# Galaxydrive.net
KiCad netlist of a schematic drawn in EAGLE
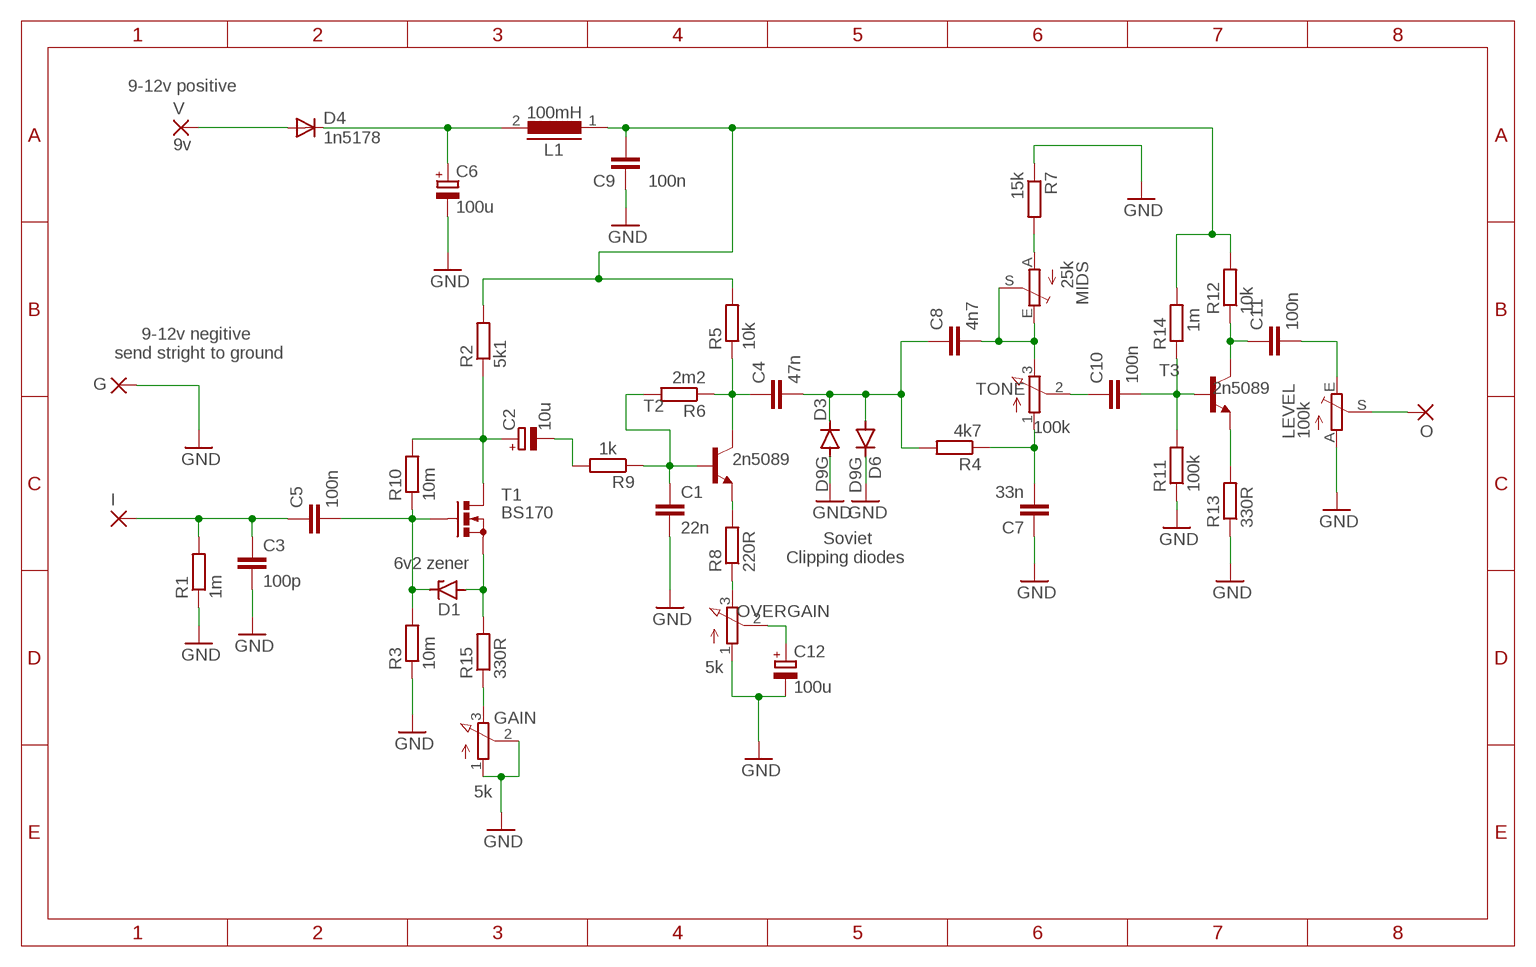
[diagram p0: schematic, sheet 1]

(export (version "E")
  (design (tool "Eeschema 10.0.6"))
  (components
    (comp (ref "C1")
      (value "22n")
      (footprint "eagle-import:C5B2.5")
      (libsource (lib "eagle-import") (part "C5/2.5"))
    )
    (comp (ref "C2")
      (value "10u")
      (footprint "eagle-import:E1,8-4")
      (libsource (lib "eagle-import") (part "CPOL-EUE1.8-4"))
    )
    (comp (ref "C3")
      (value "100p")
      (footprint "eagle-import:C5B2.5")
      (libsource (lib "eagle-import") (part "C5/2.5"))
    )
    (comp (ref "C4")
      (value "47n")
      (footprint "eagle-import:C5B2.5")
      (libsource (lib "eagle-import") (part "C5/2.5"))
    )
    (comp (ref "C5")
      (value "100n")
      (footprint "eagle-import:C5B2.5")
      (libsource (lib "eagle-import") (part "C5/2.5"))
    )
    (comp (ref "C6")
      (value "100u")
      (footprint "eagle-import:E2-4")
      (libsource (lib "eagle-import") (part "CPOL-EUE2-4"))
    )
    (comp (ref "C7")
      (value "33n")
      (footprint "eagle-import:C5B2.5")
      (libsource (lib "eagle-import") (part "C5/2.5"))
    )
    (comp (ref "C8")
      (value "4n7")
      (footprint "eagle-import:C5B2.5")
      (libsource (lib "eagle-import") (part "C5/2.5"))
    )
    (comp (ref "C9")
      (value "100n")
      (footprint "eagle-import:C5B2.5")
      (libsource (lib "eagle-import") (part "C5/2.5"))
    )
    (comp (ref "C10")
      (value "100n")
      (footprint "eagle-import:C5B2.5")
      (libsource (lib "eagle-import") (part "C5/2.5"))
    )
    (comp (ref "C11")
      (value "100n")
      (footprint "eagle-import:C5B2.5")
      (libsource (lib "eagle-import") (part "C5/2.5"))
    )
    (comp (ref "C12")
      (value "100u")
      (footprint "eagle-import:E2-4")
      (libsource (lib "eagle-import") (part "CPOL-EUE2-4"))
    )
    (comp (ref "D1")
      (value "6v2 zener")
      (footprint "eagle-import:DO34Z7")
      (libsource (lib "eagle-import") (part "BZX90"))
    )
    (comp (ref "D3")
      (value "D9G")
      (footprint "eagle-import:DO07")
      (libsource (lib "eagle-import") (part "OA91"))
    )
    (comp (ref "D4")
      (value "1n5178")
      (footprint "eagle-import:D-7.5")
      (libsource (lib "eagle-import") (part "DIODE-D-7.5"))
    )
    (comp (ref "D6")
      (value "D9G")
      (footprint "eagle-import:DO07")
      (libsource (lib "eagle-import") (part "OA91"))
    )
    (comp (ref "G")
      (value "2,15/1,0")
      (footprint "eagle-import:2,15_1,0")
      (libsource (lib "eagle-import") (part "2,15/1,0"))
    )
    (comp (ref "GAIN")
      (value "5k")
      (footprint "eagle-import:3RP_1610N")
      (libsource (lib "eagle-import") (part "HEXPOT1"))
    )
    (comp (ref "I")
      (value "2,15/1,0")
      (footprint "eagle-import:2,15_1,0")
      (libsource (lib "eagle-import") (part "2,15/1,0"))
    )
    (comp (ref "L1")
      (value "100mH")
      (footprint "eagle-import:MCC10")
      (libsource (lib "eagle-import") (part "MCC10"))
    )
    (comp (ref "LEVEL")
      (value "100k")
      (footprint "eagle-import:B25P")
      (libsource (lib "eagle-import") (part "TRIM_EU-B25P"))
    )
    (comp (ref "MIDS")
      (value "25k")
      (footprint "eagle-import:B25P")
      (libsource (lib "eagle-import") (part "TRIM_EU-B25P"))
    )
    (comp (ref "O")
      (value "2,15/1,0")
      (footprint "eagle-import:2,15_1,0")
      (libsource (lib "eagle-import") (part "2,15/1,0"))
    )
    (comp (ref "OVERGAIN")
      (value "5k")
      (footprint "eagle-import:3RP_1610N")
      (libsource (lib "eagle-import") (part "HEXPOT1"))
    )
    (comp (ref "R1")
      (value "1m")
      (footprint "eagle-import:0207_7")
      (libsource (lib "eagle-import") (part "R-EU_0207/7"))
    )
    (comp (ref "R2")
      (value "5k1")
      (footprint "eagle-import:0207_7")
      (libsource (lib "eagle-import") (part "R-EU_0207/7"))
    )
    (comp (ref "R3")
      (value "10m")
      (footprint "eagle-import:0207_7")
      (libsource (lib "eagle-import") (part "R-EU_0207/7"))
    )
    (comp (ref "R4")
      (value "4k7")
      (footprint "eagle-import:0207_7")
      (libsource (lib "eagle-import") (part "R-EU_0207/7"))
    )
    (comp (ref "R5")
      (value "10k")
      (footprint "eagle-import:0207_7")
      (libsource (lib "eagle-import") (part "R-EU_0207/7"))
    )
    (comp (ref "R6")
      (value "2m2")
      (footprint "eagle-import:0207_7")
      (libsource (lib "eagle-import") (part "R-EU_0207/7"))
    )
    (comp (ref "R7")
      (value "15k")
      (footprint "eagle-import:0207_7")
      (libsource (lib "eagle-import") (part "R-EU_0207/7"))
    )
    (comp (ref "R8")
      (value "220R")
      (footprint "eagle-import:0207_7")
      (libsource (lib "eagle-import") (part "R-EU_0207/7"))
    )
    (comp (ref "R9")
      (value "1k")
      (footprint "eagle-import:0207_7")
      (libsource (lib "eagle-import") (part "R-EU_0207/7"))
    )
    (comp (ref "R10")
      (value "10m")
      (footprint "eagle-import:0207_7")
      (libsource (lib "eagle-import") (part "R-EU_0207/7"))
    )
    (comp (ref "R11")
      (value "100k")
      (footprint "eagle-import:0207_7")
      (libsource (lib "eagle-import") (part "R-EU_0207/7"))
    )
    (comp (ref "R12")
      (value "10k")
      (footprint "eagle-import:0207_7")
      (libsource (lib "eagle-import") (part "R-EU_0207/7"))
    )
    (comp (ref "R13")
      (value "330R")
      (footprint "eagle-import:0207_7")
      (libsource (lib "eagle-import") (part "R-EU_0207/7"))
    )
    (comp (ref "R14")
      (value "1m")
      (footprint "eagle-import:0207_7")
      (libsource (lib "eagle-import") (part "R-EU_0207/7"))
    )
    (comp (ref "R15")
      (value "330R")
      (footprint "eagle-import:0207_7")
      (libsource (lib "eagle-import") (part "R-EU_0207/7"))
    )
    (comp (ref "T1")
      (value "BS170")
      (footprint "eagle-import:SOT54E")
      (libsource (lib "eagle-import") (part "BS170"))
    )
    (comp (ref "T2")
      (value "2n5089")
      (footprint "eagle-import:TO92")
      (libsource (lib "eagle-import") (part "2N3904"))
    )
    (comp (ref "T3")
      (value "2n5089")
      (footprint "eagle-import:TO92")
      (libsource (lib "eagle-import") (part "2N3904"))
    )
    (comp (ref "TONE")
      (value "100k")
      (footprint "eagle-import:3RP_1610N")
      (libsource (lib "eagle-import") (part "HEXPOT1"))
    )
    (comp (ref "V")
      (value "9v")
      (footprint "eagle-import:2,15_1,0")
      (libsource (lib "eagle-import") (part "2,15/1,0"))
    )
  )
  (nets
    (net (code "1") (name "GND") (class "Default")
      (node (ref "C1") (pin "2") (pinfunction "2_2") (pintype "passive"))
      (node (ref "C12") (pin "-") (pinfunction "-_-") (pintype "passive"))
      (node (ref "C3") (pin "2") (pinfunction "2_2") (pintype "passive"))
      (node (ref "C6") (pin "-") (pinfunction "-_-") (pintype "passive"))
      (node (ref "C7") (pin "1") (pinfunction "1_1") (pintype "passive"))
      (node (ref "C9") (pin "1") (pinfunction "1_1") (pintype "passive"))
      (node (ref "D3") (pin "A") (pinfunction "A_A") (pintype "passive"))
      (node (ref "D6") (pin "C") (pinfunction "C_C") (pintype "passive"))
      (node (ref "G") (pin "1") (pinfunction "P_1") (pintype "passive"))
      (node (ref "GAIN") (pin "1") (pinfunction "A_1") (pintype "passive"))
      (node (ref "GAIN") (pin "2") (pinfunction "S_2") (pintype "passive"))
      (node (ref "LEVEL") (pin "A") (pinfunction "A_A") (pintype "passive"))
      (node (ref "OVERGAIN") (pin "1") (pinfunction "A_1") (pintype "passive"))
      (node (ref "R1") (pin "1") (pinfunction "1_1") (pintype "passive"))
      (node (ref "R11") (pin "1") (pinfunction "1_1") (pintype "passive"))
      (node (ref "R13") (pin "1") (pinfunction "1_1") (pintype "passive"))
      (node (ref "R3") (pin "1") (pinfunction "1_1") (pintype "passive"))
      (node (ref "R7") (pin "1") (pinfunction "1_1") (pintype "passive"))
    )
    (net (code "2") (name "Net-(C2-Pad+)") (class "Default")
      (node (ref "C2") (pin "+") (pinfunction "+_+") (pintype "passive"))
      (node (ref "R10") (pin "2") (pinfunction "2_2") (pintype "passive"))
      (node (ref "R2") (pin "1") (pinfunction "1_1") (pintype "passive"))
      (node (ref "T1") (pin "D") (pinfunction "D_D") (pintype "passive"))
    )
    (net (code "3") (name "Net-(C2-Pad-)") (class "Default")
      (node (ref "C2") (pin "-") (pinfunction "-_-") (pintype "passive"))
      (node (ref "R9") (pin "2") (pinfunction "2_2") (pintype "passive"))
    )
    (net (code "4") (name "Net-(C4-Pad2)") (class "Default")
      (node (ref "C4") (pin "2") (pinfunction "2_2") (pintype "passive"))
      (node (ref "C8") (pin "1") (pinfunction "1_1") (pintype "passive"))
      (node (ref "D3") (pin "C") (pinfunction "C_C") (pintype "passive"))
      (node (ref "D6") (pin "A") (pinfunction "A_A") (pintype "passive"))
      (node (ref "R4") (pin "2") (pinfunction "2_2") (pintype "passive"))
    )
    (net (code "5") (name "Net-(C5-Pad2)") (class "Default")
      (node (ref "C5") (pin "2") (pinfunction "2_2") (pintype "passive"))
      (node (ref "D1") (pin "C") (pinfunction "C_C") (pintype "passive"))
      (node (ref "R10") (pin "1") (pinfunction "1_1") (pintype "passive"))
      (node (ref "R3") (pin "2") (pinfunction "2_2") (pintype "passive"))
      (node (ref "T1") (pin "G") (pinfunction "G_G") (pintype "passive"))
    )
    (net (code "6") (name "Net-(C6-Pad+)") (class "Default")
      (node (ref "C6") (pin "+") (pinfunction "+_+") (pintype "passive"))
      (node (ref "D4") (pin "C") (pinfunction "C_C") (pintype "passive"))
      (node (ref "L1") (pin "2") (pinfunction "2_2") (pintype "passive"))
    )
    (net (code "7") (name "Net-(C9-Pad2)") (class "Default")
      (node (ref "C9") (pin "2") (pinfunction "2_2") (pintype "passive"))
      (node (ref "L1") (pin "1") (pinfunction "1_1") (pintype "passive"))
      (node (ref "R12") (pin "2") (pinfunction "2_2") (pintype "passive"))
      (node (ref "R14") (pin "2") (pinfunction "2_2") (pintype "passive"))
      (node (ref "R2") (pin "2") (pinfunction "2_2") (pintype "passive"))
      (node (ref "R5") (pin "2") (pinfunction "2_2") (pintype "passive"))
    )
    (net (code "8") (name "Net-(C11-Pad2)") (class "Default")
      (node (ref "C11") (pin "2") (pinfunction "2_2") (pintype "passive"))
      (node (ref "LEVEL") (pin "E") (pinfunction "E_E") (pintype "passive"))
    )
    (net (code "9") (name "Net-(D1-PadA)") (class "Default")
      (node (ref "D1") (pin "A") (pinfunction "A_A") (pintype "passive"))
      (node (ref "R15") (pin "2") (pinfunction "2_2") (pintype "passive"))
      (node (ref "T1") (pin "S") (pinfunction "S_S") (pintype "passive"))
    )
    (net (code "10") (name "Net-(GAIN-E)") (class "Default")
      (node (ref "GAIN") (pin "3") (pinfunction "E_3") (pintype "passive"))
      (node (ref "R15") (pin "1") (pinfunction "1_1") (pintype "passive"))
    )
    (net (code "11") (name "Net-(I-P)") (class "Default")
      (node (ref "C3") (pin "1") (pinfunction "1_1") (pintype "passive"))
      (node (ref "C5") (pin "1") (pinfunction "1_1") (pintype "passive"))
      (node (ref "I") (pin "1") (pinfunction "P_1") (pintype "passive"))
      (node (ref "R1") (pin "2") (pinfunction "2_2") (pintype "passive"))
    )
    (net (code "12") (name "Net-(MIDS-PadA)") (class "Default")
      (node (ref "MIDS") (pin "A") (pinfunction "A_A") (pintype "passive"))
      (node (ref "R7") (pin "2") (pinfunction "2_2") (pintype "passive"))
    )
    (net (code "13") (name "Net-(O-P)") (class "Default")
      (node (ref "LEVEL") (pin "S") (pinfunction "S_S") (pintype "passive"))
      (node (ref "O") (pin "1") (pinfunction "P_1") (pintype "passive"))
    )
    (net (code "14") (name "Net-(OVERGAIN-E)") (class "Default")
      (node (ref "OVERGAIN") (pin "3") (pinfunction "E_3") (pintype "passive"))
      (node (ref "R8") (pin "1") (pinfunction "1_1") (pintype "passive"))
    )
    (net (code "15") (name "Net-(OVERGAIN-S)") (class "Default")
      (node (ref "C12") (pin "+") (pinfunction "+_+") (pintype "passive"))
      (node (ref "OVERGAIN") (pin "2") (pinfunction "S_2") (pintype "passive"))
    )
    (net (code "16") (name "Net-(T2-B)") (class "Default")
      (node (ref "C1") (pin "1") (pinfunction "1_1") (pintype "passive"))
      (node (ref "R6") (pin "2") (pinfunction "2_2") (pintype "passive"))
      (node (ref "R9") (pin "1") (pinfunction "1_1") (pintype "passive"))
      (node (ref "T2") (pin "2") (pinfunction "B_2") (pintype "passive"))
    )
    (net (code "17") (name "Net-(T2-C)") (class "Default")
      (node (ref "C4") (pin "1") (pinfunction "1_1") (pintype "passive"))
      (node (ref "R5") (pin "1") (pinfunction "1_1") (pintype "passive"))
      (node (ref "R6") (pin "1") (pinfunction "1_1") (pintype "passive"))
      (node (ref "T2") (pin "1") (pinfunction "C_1") (pintype "passive"))
    )
    (net (code "18") (name "Net-(T2-E)") (class "Default")
      (node (ref "R8") (pin "2") (pinfunction "2_2") (pintype "passive"))
      (node (ref "T2") (pin "3") (pinfunction "E_3") (pintype "passive"))
    )
    (net (code "19") (name "Net-(T3-B)") (class "Default")
      (node (ref "C10") (pin "2") (pinfunction "2_2") (pintype "passive"))
      (node (ref "R11") (pin "2") (pinfunction "2_2") (pintype "passive"))
      (node (ref "R14") (pin "1") (pinfunction "1_1") (pintype "passive"))
      (node (ref "T3") (pin "2") (pinfunction "B_2") (pintype "passive"))
    )
    (net (code "20") (name "Net-(T3-C)") (class "Default")
      (node (ref "C11") (pin "1") (pinfunction "1_1") (pintype "passive"))
      (node (ref "R12") (pin "1") (pinfunction "1_1") (pintype "passive"))
      (node (ref "T3") (pin "1") (pinfunction "C_1") (pintype "passive"))
    )
    (net (code "21") (name "Net-(T3-E)") (class "Default")
      (node (ref "R13") (pin "2") (pinfunction "2_2") (pintype "passive"))
      (node (ref "T3") (pin "3") (pinfunction "E_3") (pintype "passive"))
    )
    (net (code "22") (name "Net-(TONE-A)") (class "Default")
      (node (ref "C7") (pin "2") (pinfunction "2_2") (pintype "passive"))
      (node (ref "R4") (pin "1") (pinfunction "1_1") (pintype "passive"))
      (node (ref "TONE") (pin "1") (pinfunction "A_1") (pintype "passive"))
    )
    (net (code "23") (name "Net-(TONE-E)") (class "Default")
      (node (ref "C8") (pin "2") (pinfunction "2_2") (pintype "passive"))
      (node (ref "MIDS") (pin "E") (pinfunction "E_E") (pintype "passive"))
      (node (ref "MIDS") (pin "S") (pinfunction "S_S") (pintype "passive"))
      (node (ref "TONE") (pin "3") (pinfunction "E_3") (pintype "passive"))
    )
    (net (code "24") (name "Net-(TONE-S)") (class "Default")
      (node (ref "C10") (pin "1") (pinfunction "1_1") (pintype "passive"))
      (node (ref "TONE") (pin "2") (pinfunction "S_2") (pintype "passive"))
    )
    (net (code "25") (name "Net-(V-P)") (class "Default")
      (node (ref "D4") (pin "A") (pinfunction "A_A") (pintype "passive"))
      (node (ref "V") (pin "1") (pinfunction "P_1") (pintype "passive"))
    )
  )
)
